# Tilty_Omni.net
KiCad netlist of a schematic drawn in EAGLE
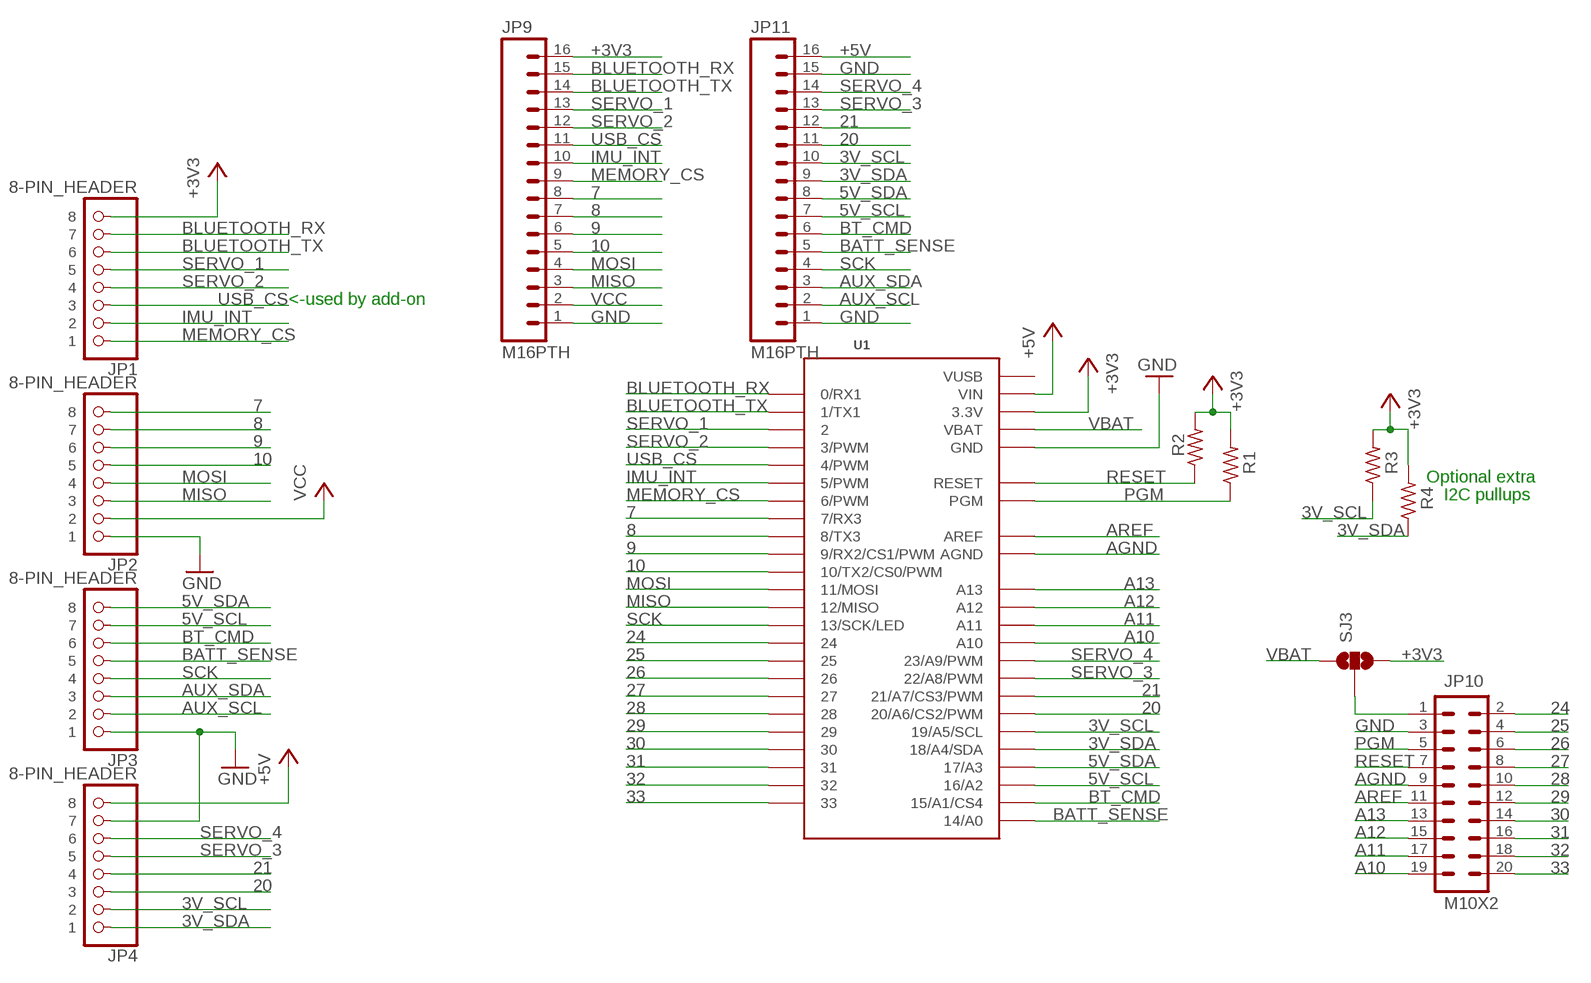
[diagram p0: schematic, sheet 1]

(export (version "E")
  (design (tool "Eeschema 10.0.6"))
  (components
    (comp (ref "JP1")
      (value "8-PIN_HEADER")
      (footprint "eagle-import:8-PIN_RECEPTACLE_LOCK_NO-SS")
      (libsource (lib "eagle-import") (part "8-PIN_HEADER"))
    )
    (comp (ref "JP2")
      (value "8-PIN_HEADER")
      (footprint "eagle-import:8-PIN_RECEPTACLE_LOCK_NO-SS")
      (libsource (lib "eagle-import") (part "8-PIN_HEADER"))
    )
    (comp (ref "JP3")
      (value "8-PIN_HEADER")
      (footprint "eagle-import:8-PIN_RECEPTACLE_LOCK_NO-SS")
      (libsource (lib "eagle-import") (part "8-PIN_HEADER"))
    )
    (comp (ref "JP4")
      (value "8-PIN_HEADER")
      (footprint "eagle-import:8-PIN_RECEPTACLE_LOCK_NO-SS")
      (libsource (lib "eagle-import") (part "8-PIN_HEADER"))
    )
    (comp (ref "JP9")
      (value "M16PTH")
      (footprint "eagle-import:1X16")
      (libsource (lib "eagle-import") (part "M16PTH"))
    )
    (comp (ref "JP10")
      (value "M10X2")
      (footprint "eagle-import:2X10")
      (libsource (lib "eagle-import") (part "M10X2"))
    )
    (comp (ref "JP11")
      (value "M16PTH")
      (footprint "eagle-import:1X16")
      (libsource (lib "eagle-import") (part "M16PTH"))
    )
    (comp (ref "R1")
      (value "10k")
      (footprint "eagle-import:R0603")
      (libsource (lib "eagle-import") (part "R-US_R0603"))
    )
    (comp (ref "R2")
      (value "10k")
      (footprint "eagle-import:R0603")
      (libsource (lib "eagle-import") (part "R-US_R0603"))
    )
    (comp (ref "R3")
      (value "10k")
      (footprint "eagle-import:R0603")
      (libsource (lib "eagle-import") (part "R-US_R0603"))
    )
    (comp (ref "R4")
      (value "10k")
      (footprint "eagle-import:R0603")
      (libsource (lib "eagle-import") (part "R-US_R0603"))
    )
    (comp (ref "SJ3")
      (value "SOLDERJUMPER_2WAYPASTE2&3")
      (footprint "eagle-import:SJ_3_PASTE2&3")
      (libsource (lib "eagle-import") (part "SOLDERJUMPER_2WAYPASTE2&3"))
    )
    (comp (ref "U1")
      (value "TEENSY_3.0_ALLPINS")
      (footprint "eagle-import:TEENSY_3.0_ALLPINS")
      (libsource (lib "eagle-import") (part "TEENSY_3.0_ALLPINS"))
    )
  )
  (nets
    (net (code "1") (name "+3V3") (class "Default")
      (node (ref "JP1") (pin "P$8") (pinfunction "8_P$8") (pintype "passive"))
      (node (ref "JP9") (pin "16") (pinfunction "16_16") (pintype "passive"))
      (node (ref "R1") (pin "2") (pinfunction "2_2") (pintype "passive"))
      (node (ref "R2") (pin "2") (pinfunction "2_2") (pintype "passive"))
      (node (ref "R3") (pin "2") (pinfunction "2_2") (pintype "passive"))
      (node (ref "R4") (pin "2") (pinfunction "2_2") (pintype "passive"))
      (node (ref "SJ3") (pin "3") (pinfunction "3_3") (pintype "passive"))
      (node (ref "U1") (pin "3.3V") (pinfunction "3.3V_3.3V") (pintype "power_in"))
      (node (ref "U1") (pin "3.3V1") (pinfunction "3.3V_3.3V1") (pintype "power_in"))
      (node (ref "U1") (pin "3.3V2") (pinfunction "3.3V_3.3V2") (pintype "power_in"))
    )
    (net (code "2") (name "+5V") (class "Default")
      (node (ref "JP11") (pin "16") (pinfunction "16_16") (pintype "passive"))
      (node (ref "JP4") (pin "P$8") (pinfunction "8_P$8") (pintype "passive"))
      (node (ref "U1") (pin "VIN") (pinfunction "VIN_VIN") (pintype "power_in"))
    )
    (net (code "3") (name "/3V_SCL") (class "Default")
      (node (ref "JP11") (pin "10") (pinfunction "10_10") (pintype "passive"))
      (node (ref "JP4") (pin "P$2") (pinfunction "2_P$2") (pintype "passive"))
      (node (ref "R3") (pin "1") (pinfunction "1_1") (pintype "passive"))
      (node (ref "U1") (pin "19/A5") (pinfunction "19/A5/SCL_19/A5") (pintype "bidirectional"))
    )
    (net (code "4") (name "/3V_SDA") (class "Default")
      (node (ref "JP11") (pin "9") (pinfunction "9_9") (pintype "passive"))
      (node (ref "JP4") (pin "P$1") (pinfunction "1_P$1") (pintype "passive"))
      (node (ref "R4") (pin "1") (pinfunction "1_1") (pintype "passive"))
      (node (ref "U1") (pin "18/A4") (pinfunction "18/A4/SDA_18/A4") (pintype "bidirectional"))
    )
    (net (code "5") (name "/5V_SCL") (class "Default")
      (node (ref "JP11") (pin "7") (pinfunction "7_7") (pintype "passive"))
      (node (ref "JP3") (pin "P$7") (pinfunction "7_P$7") (pintype "passive"))
      (node (ref "U1") (pin "16/A2") (pinfunction "16/A2_16/A2") (pintype "bidirectional"))
    )
    (net (code "6") (name "/5V_SDA") (class "Default")
      (node (ref "JP11") (pin "8") (pinfunction "8_8") (pintype "passive"))
      (node (ref "JP3") (pin "P$8") (pinfunction "8_P$8") (pintype "passive"))
      (node (ref "U1") (pin "17/A3") (pinfunction "17/A3_17/A3") (pintype "bidirectional"))
    )
    (net (code "7") (name "/7") (class "Default")
      (node (ref "JP2") (pin "P$8") (pinfunction "8_P$8") (pintype "passive"))
      (node (ref "JP9") (pin "8") (pinfunction "8_8") (pintype "passive"))
      (node (ref "U1") (pin "7") (pinfunction "7/RX3_7") (pintype "bidirectional"))
    )
    (net (code "8") (name "/8") (class "Default")
      (node (ref "JP2") (pin "P$7") (pinfunction "7_P$7") (pintype "passive"))
      (node (ref "JP9") (pin "7") (pinfunction "7_7") (pintype "passive"))
      (node (ref "U1") (pin "8") (pinfunction "8/TX3_8") (pintype "bidirectional"))
    )
    (net (code "9") (name "/9") (class "Default")
      (node (ref "JP2") (pin "P$6") (pinfunction "6_P$6") (pintype "passive"))
      (node (ref "JP9") (pin "6") (pinfunction "6_6") (pintype "passive"))
      (node (ref "U1") (pin "9") (pinfunction "9/RX2/CS1/PWM_9") (pintype "bidirectional"))
    )
    (net (code "10") (name "/10") (class "Default")
      (node (ref "JP2") (pin "P$5") (pinfunction "5_P$5") (pintype "passive"))
      (node (ref "JP9") (pin "5") (pinfunction "5_5") (pintype "passive"))
      (node (ref "U1") (pin "10") (pinfunction "10/TX2/CS0/PWM_10") (pintype "bidirectional"))
    )
    (net (code "11") (name "/20") (class "Default")
      (node (ref "JP11") (pin "11") (pinfunction "11_11") (pintype "passive"))
      (node (ref "JP4") (pin "P$3") (pinfunction "3_P$3") (pintype "passive"))
      (node (ref "U1") (pin "20/A6") (pinfunction "20/A6/CS2/PWM_20/A6") (pintype "bidirectional"))
    )
    (net (code "12") (name "/21") (class "Default")
      (node (ref "JP11") (pin "12") (pinfunction "12_12") (pintype "passive"))
      (node (ref "JP4") (pin "P$4") (pinfunction "4_P$4") (pintype "passive"))
      (node (ref "U1") (pin "21/A7") (pinfunction "21/A7/CS3/PWM_21/A7") (pintype "bidirectional"))
    )
    (net (code "13") (name "/24") (class "Default")
      (node (ref "JP10") (pin "2") (pinfunction "2_2") (pintype "passive"))
      (node (ref "U1") (pin "24") (pinfunction "24_24") (pintype "bidirectional"))
    )
    (net (code "14") (name "/25") (class "Default")
      (node (ref "JP10") (pin "4") (pinfunction "4_4") (pintype "passive"))
      (node (ref "U1") (pin "25") (pinfunction "25_25") (pintype "bidirectional"))
    )
    (net (code "15") (name "/26") (class "Default")
      (node (ref "JP10") (pin "6") (pinfunction "6_6") (pintype "passive"))
      (node (ref "U1") (pin "26") (pinfunction "26_26") (pintype "bidirectional"))
    )
    (net (code "16") (name "/27") (class "Default")
      (node (ref "JP10") (pin "8") (pinfunction "8_8") (pintype "passive"))
      (node (ref "U1") (pin "27") (pinfunction "27_27") (pintype "bidirectional"))
    )
    (net (code "17") (name "/28") (class "Default")
      (node (ref "JP10") (pin "10") (pinfunction "10_10") (pintype "passive"))
      (node (ref "U1") (pin "28") (pinfunction "28_28") (pintype "bidirectional"))
    )
    (net (code "18") (name "/29") (class "Default")
      (node (ref "JP10") (pin "12") (pinfunction "12_12") (pintype "passive"))
      (node (ref "U1") (pin "29") (pinfunction "29_29") (pintype "bidirectional"))
    )
    (net (code "19") (name "/30") (class "Default")
      (node (ref "JP10") (pin "14") (pinfunction "14_14") (pintype "passive"))
      (node (ref "U1") (pin "30") (pinfunction "30_30") (pintype "bidirectional"))
    )
    (net (code "20") (name "/31") (class "Default")
      (node (ref "JP10") (pin "16") (pinfunction "16_16") (pintype "passive"))
      (node (ref "U1") (pin "31") (pinfunction "31_31") (pintype "bidirectional"))
    )
    (net (code "21") (name "/32") (class "Default")
      (node (ref "JP10") (pin "18") (pinfunction "18_18") (pintype "passive"))
      (node (ref "U1") (pin "32") (pinfunction "32_32") (pintype "bidirectional"))
    )
    (net (code "22") (name "/33") (class "Default")
      (node (ref "JP10") (pin "20") (pinfunction "20_20") (pintype "passive"))
      (node (ref "U1") (pin "33") (pinfunction "33_33") (pintype "bidirectional"))
    )
    (net (code "23") (name "/A10") (class "Default")
      (node (ref "JP10") (pin "19") (pinfunction "19_19") (pintype "passive"))
      (node (ref "U1") (pin "A10") (pinfunction "A10_A10") (pintype "bidirectional"))
    )
    (net (code "24") (name "/A11") (class "Default")
      (node (ref "JP10") (pin "17") (pinfunction "17_17") (pintype "passive"))
      (node (ref "U1") (pin "A11") (pinfunction "A11_A11") (pintype "bidirectional"))
    )
    (net (code "25") (name "/A12") (class "Default")
      (node (ref "JP10") (pin "15") (pinfunction "15_15") (pintype "passive"))
      (node (ref "U1") (pin "A12") (pinfunction "A12_A12") (pintype "bidirectional"))
    )
    (net (code "26") (name "/A13") (class "Default")
      (node (ref "JP10") (pin "13") (pinfunction "13_13") (pintype "passive"))
      (node (ref "U1") (pin "A13") (pinfunction "A13_A13") (pintype "bidirectional"))
    )
    (net (code "27") (name "/AGND") (class "Default")
      (node (ref "JP10") (pin "9") (pinfunction "9_9") (pintype "passive"))
      (node (ref "U1") (pin "AGND") (pinfunction "AGND_AGND") (pintype "power_in"))
    )
    (net (code "28") (name "/AREF") (class "Default")
      (node (ref "JP10") (pin "11") (pinfunction "11_11") (pintype "passive"))
      (node (ref "U1") (pin "AREF") (pinfunction "AREF_AREF") (pintype "power_in"))
    )
    (net (code "29") (name "/AUX_SCL") (class "Default")
      (node (ref "JP11") (pin "2") (pinfunction "2_2") (pintype "passive"))
      (node (ref "JP3") (pin "P$2") (pinfunction "2_P$2") (pintype "passive"))
    )
    (net (code "30") (name "/AUX_SDA") (class "Default")
      (node (ref "JP11") (pin "3") (pinfunction "3_3") (pintype "passive"))
      (node (ref "JP3") (pin "P$3") (pinfunction "3_P$3") (pintype "passive"))
    )
    (net (code "31") (name "/BATT_SENSE") (class "Default")
      (node (ref "JP11") (pin "5") (pinfunction "5_5") (pintype "passive"))
      (node (ref "JP3") (pin "P$5") (pinfunction "5_P$5") (pintype "passive"))
      (node (ref "U1") (pin "14/A0") (pinfunction "14/A0_14/A0") (pintype "bidirectional"))
    )
    (net (code "32") (name "/BLUETOOTH_RX") (class "Default")
      (node (ref "JP1") (pin "P$7") (pinfunction "7_P$7") (pintype "passive"))
      (node (ref "JP9") (pin "15") (pinfunction "15_15") (pintype "passive"))
      (node (ref "U1") (pin "0") (pinfunction "0/RX1_0") (pintype "bidirectional"))
    )
    (net (code "33") (name "/BLUETOOTH_TX") (class "Default")
      (node (ref "JP1") (pin "P$6") (pinfunction "6_P$6") (pintype "passive"))
      (node (ref "JP9") (pin "14") (pinfunction "14_14") (pintype "passive"))
      (node (ref "U1") (pin "1") (pinfunction "1/TX1_1") (pintype "bidirectional"))
    )
    (net (code "34") (name "/BT_CMD") (class "Default")
      (node (ref "JP11") (pin "6") (pinfunction "6_6") (pintype "passive"))
      (node (ref "JP3") (pin "P$6") (pinfunction "6_P$6") (pintype "passive"))
      (node (ref "U1") (pin "15/A1") (pinfunction "15/A1/CS4_15/A1") (pintype "bidirectional"))
    )
    (net (code "35") (name "/IMU_INT") (class "Default")
      (node (ref "JP1") (pin "P$2") (pinfunction "2_P$2") (pintype "passive"))
      (node (ref "JP9") (pin "10") (pinfunction "10_10") (pintype "passive"))
      (node (ref "U1") (pin "5") (pinfunction "5/PWM_5") (pintype "bidirectional"))
    )
    (net (code "36") (name "/MEMORY_CS") (class "Default")
      (node (ref "JP1") (pin "P$1") (pinfunction "1_P$1") (pintype "passive"))
      (node (ref "JP9") (pin "9") (pinfunction "9_9") (pintype "passive"))
      (node (ref "U1") (pin "6") (pinfunction "6/PWM_6") (pintype "bidirectional"))
    )
    (net (code "37") (name "/MISO") (class "Default")
      (node (ref "JP2") (pin "P$3") (pinfunction "3_P$3") (pintype "passive"))
      (node (ref "JP9") (pin "3") (pinfunction "3_3") (pintype "passive"))
      (node (ref "U1") (pin "12") (pinfunction "12/MISO_12") (pintype "bidirectional"))
    )
    (net (code "38") (name "/MOSI") (class "Default")
      (node (ref "JP2") (pin "P$4") (pinfunction "4_P$4") (pintype "passive"))
      (node (ref "JP9") (pin "4") (pinfunction "4_4") (pintype "passive"))
      (node (ref "U1") (pin "11") (pinfunction "11/MOSI_11") (pintype "bidirectional"))
    )
    (net (code "39") (name "/PGM") (class "Default")
      (node (ref "JP10") (pin "5") (pinfunction "5_5") (pintype "passive"))
      (node (ref "R1") (pin "1") (pinfunction "1_1") (pintype "passive"))
      (node (ref "U1") (pin "PGM") (pinfunction "PGM_PGM") (pintype "bidirectional"))
    )
    (net (code "40") (name "/RESET") (class "Default")
      (node (ref "JP10") (pin "7") (pinfunction "7_7") (pintype "passive"))
      (node (ref "R2") (pin "1") (pinfunction "1_1") (pintype "passive"))
      (node (ref "U1") (pin "RESET") (pinfunction "RESET_RESET") (pintype "bidirectional"))
    )
    (net (code "41") (name "/SCK") (class "Default")
      (node (ref "JP11") (pin "4") (pinfunction "4_4") (pintype "passive"))
      (node (ref "JP3") (pin "P$4") (pinfunction "4_P$4") (pintype "passive"))
      (node (ref "U1") (pin "13") (pinfunction "13/SCK/LED_13") (pintype "bidirectional"))
    )
    (net (code "42") (name "/SERVO_1") (class "Default")
      (node (ref "JP1") (pin "P$5") (pinfunction "5_P$5") (pintype "passive"))
      (node (ref "JP9") (pin "13") (pinfunction "13_13") (pintype "passive"))
      (node (ref "U1") (pin "2") (pinfunction "2_2") (pintype "bidirectional"))
    )
    (net (code "43") (name "/SERVO_2") (class "Default")
      (node (ref "JP1") (pin "P$4") (pinfunction "4_P$4") (pintype "passive"))
      (node (ref "JP9") (pin "12") (pinfunction "12_12") (pintype "passive"))
      (node (ref "U1") (pin "3") (pinfunction "3/PWM_3") (pintype "bidirectional"))
    )
    (net (code "44") (name "/SERVO_3") (class "Default")
      (node (ref "JP11") (pin "13") (pinfunction "13_13") (pintype "passive"))
      (node (ref "JP4") (pin "P$5") (pinfunction "5_P$5") (pintype "passive"))
      (node (ref "U1") (pin "22/A8") (pinfunction "22/A8/PWM_22/A8") (pintype "bidirectional"))
    )
    (net (code "45") (name "/SERVO_4") (class "Default")
      (node (ref "JP11") (pin "14") (pinfunction "14_14") (pintype "passive"))
      (node (ref "JP4") (pin "P$6") (pinfunction "6_P$6") (pintype "passive"))
      (node (ref "U1") (pin "23/A9") (pinfunction "23/A9/PWM_23/A9") (pintype "bidirectional"))
    )
    (net (code "46") (name "/USB_CS") (class "Default")
      (node (ref "JP1") (pin "P$3") (pinfunction "3_P$3") (pintype "passive"))
      (node (ref "JP9") (pin "11") (pinfunction "11_11") (pintype "passive"))
      (node (ref "U1") (pin "4") (pinfunction "4/PWM_4") (pintype "bidirectional"))
    )
    (net (code "47") (name "/VBAT") (class "Default")
      (node (ref "SJ3") (pin "1") (pinfunction "1_1") (pintype "passive"))
      (node (ref "U1") (pin "VBAT") (pinfunction "VBAT_VBAT") (pintype "power_in"))
    )
    (net (code "48") (name "/VUSB") (class "Default")
      (node (ref "U1") (pin "VUSB") (pinfunction "VUSB_VUSB") (pintype "power_in"))
    )
    (net (code "49") (name "GND") (class "Default")
      (node (ref "JP10") (pin "3") (pinfunction "3_3") (pintype "passive"))
      (node (ref "JP11") (pin "1") (pinfunction "1_1") (pintype "passive"))
      (node (ref "JP11") (pin "15") (pinfunction "15_15") (pintype "passive"))
      (node (ref "JP2") (pin "P$1") (pinfunction "1_P$1") (pintype "passive"))
      (node (ref "JP3") (pin "P$1") (pinfunction "1_P$1") (pintype "passive"))
      (node (ref "JP4") (pin "P$7") (pinfunction "7_P$7") (pintype "passive"))
      (node (ref "JP9") (pin "1") (pinfunction "1_1") (pintype "passive"))
      (node (ref "U1") (pin "GND") (pinfunction "GND_GND") (pintype "power_in"))
      (node (ref "U1") (pin "GND1") (pinfunction "GND_GND1") (pintype "power_in"))
      (node (ref "U1") (pin "GND2") (pinfunction "GND_GND2") (pintype "power_in"))
    )
    (net (code "50") (name "Net-(JP10-Pad1)") (class "Default")
      (node (ref "JP10") (pin "1") (pinfunction "1_1") (pintype "passive"))
      (node (ref "SJ3") (pin "2") (pinfunction "2_2") (pintype "passive"))
    )
    (net (code "51") (name "VCC") (class "Default")
      (node (ref "JP2") (pin "P$2") (pinfunction "2_P$2") (pintype "passive"))
      (node (ref "JP9") (pin "2") (pinfunction "2_2") (pintype "passive"))
    )
  )
)
